# Alimentacion.net
KiCad netlist of a schematic drawn in Altium Designer
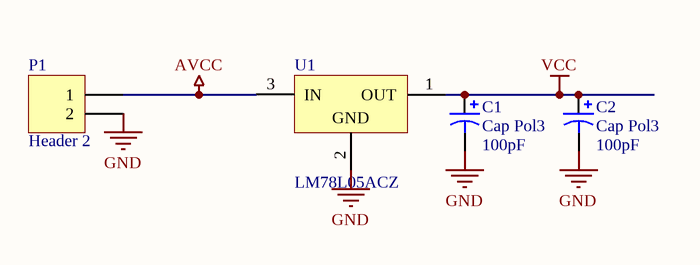
[diagram p0: Alimentacion.SchDoc]

(export (version "E")
  (design (tool "Eeschema 10.0.6"))
  (components
    (comp (ref "C1")
      (value "Cap Pol3")
      (footprint "C0805")
      (description "Polarized Capacitor (Surface Mount)")
      (fields (field (name "ALTIUM_VALUE") "100pF") (field (name "PUBLISHER") "Altium Limited"))
      (libsource (lib "Miscellaneous Devices") (part "Cap Pol3"))
    )
    (comp (ref "C2")
      (value "Cap Pol3")
      (footprint "C0805")
      (description "Polarized Capacitor (Surface Mount)")
      (fields (field (name "ALTIUM_VALUE") "100pF") (field (name "PUBLISHER") "Altium Limited"))
      (libsource (lib "Miscellaneous Devices") (part "Cap Pol3"))
    )
    (comp (ref "P1")
      (value "Header 2")
      (footprint "HDR1X2")
      (description "Header, 2-Pin")
      (fields (field (name "PUBLISHER") "Altium Limited"))
      (libsource (lib "Miscellaneous Connectors") (part "Header 2"))
    )
    (comp (ref "U1")
      (value "LM78L05ACZ")
      (footprint "Z03A")
      (description "3-Terminal Positive Regulators")
      (fields
        (field (name "MANUFACTURER") "National Semiconductor")
        (field (name "DIGIKEYPARTNUMBER") "LM78L05ACZNS-ND")
        (field (name "PUBLISHER") "Altium Limited")
      )
      (libsource (lib "NSC LDO") (part "LM78L05ACZ"))
    )
  )
  (nets
    (net (code "1") (name "AVCC") (class "Default")
      (node (ref "P1") (pin "1") (pinfunction "1_1") (pintype "passive"))
      (node (ref "U1") (pin "3") (pinfunction "IN_3") (pintype "power_in"))
    )
    (net (code "2") (name "GND") (class "Default")
      (node (ref "C1") (pin "2") (pinfunction "2_2") (pintype "passive"))
      (node (ref "C2") (pin "2") (pinfunction "2_2") (pintype "passive"))
      (node (ref "P1") (pin "2") (pinfunction "2_2") (pintype "passive"))
      (node (ref "U1") (pin "2") (pinfunction "GND_2") (pintype "power_in"))
    )
    (net (code "3") (name "VCC") (class "Default")
      (node (ref "C1") (pin "1") (pinfunction "1_1") (pintype "passive"))
      (node (ref "C2") (pin "1") (pinfunction "1_1") (pintype "passive"))
      (node (ref "U1") (pin "1") (pinfunction "OUT_1") (pintype "power_in"))
    )
  )
)
